# luxometro_16F1709.net
KiCad netlist of a schematic drawn in EAGLE
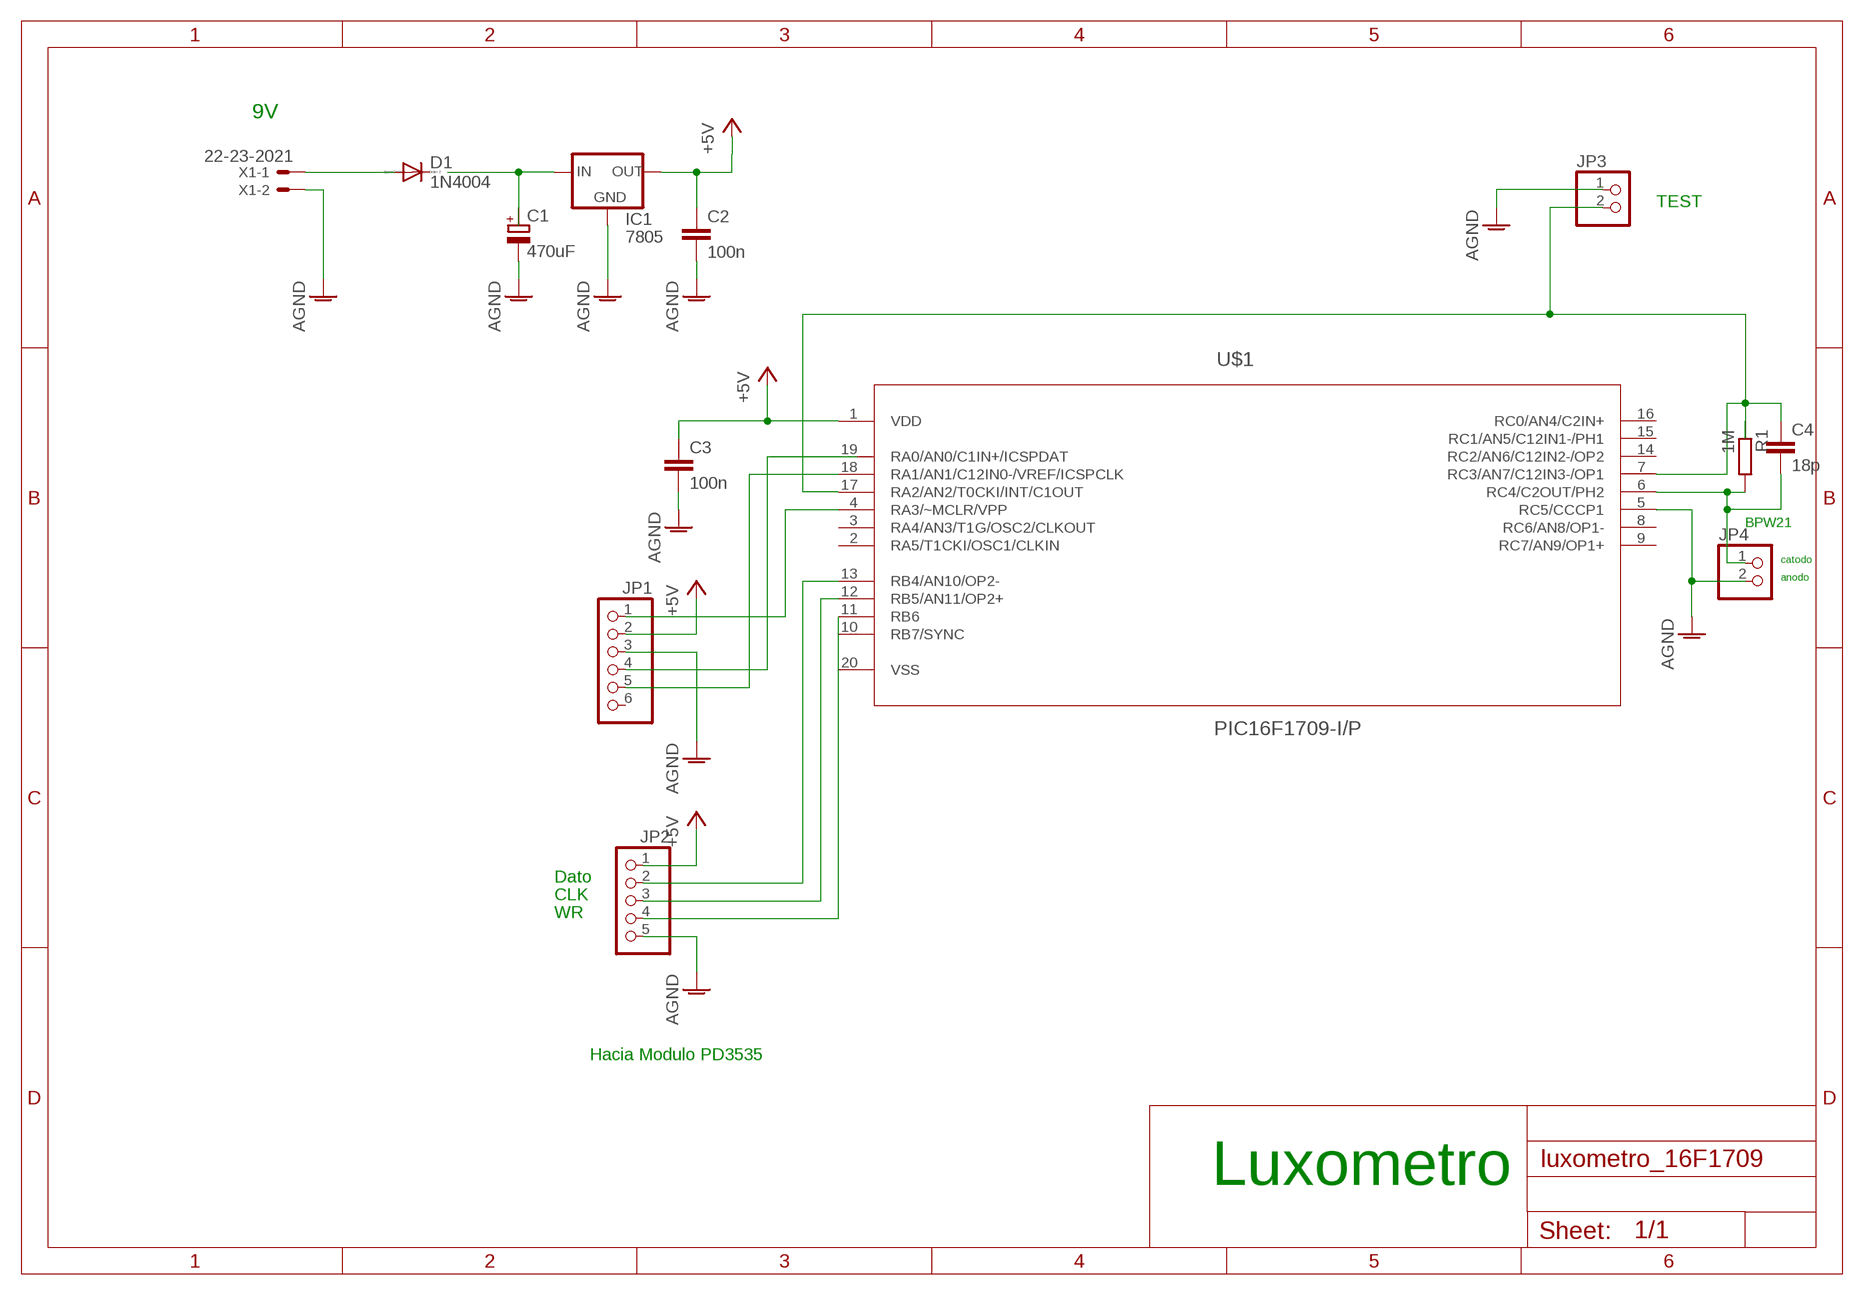
[diagram p0: schematic, sheet 1]

(export (version "E")
  (design (tool "Eeschema 10.0.6"))
  (components
    (comp (ref "C1")
      (value "470uF")
      (footprint "eagle-import:E2,5-6E")
      (libsource (lib "eagle-import") (part "CPOL-EUE2,5-6E"))
    )
    (comp (ref "C2")
      (value "100n")
      (footprint "eagle-import:C050-024X044")
      (libsource (lib "eagle-import") (part "C-EU050-024X044"))
    )
    (comp (ref "C3")
      (value "100n")
      (footprint "eagle-import:C050-024X044")
      (libsource (lib "eagle-import") (part "C-EU050-024X044"))
    )
    (comp (ref "C4")
      (value "18p")
      (footprint "eagle-import:C050-024X044")
      (libsource (lib "eagle-import") (part "C-EU050-024X044"))
    )
    (comp (ref "D1")
      (value "1N4004")
      (footprint "eagle-import:DO41-10")
      (libsource (lib "eagle-import") (part "1N4004"))
    )
    (comp (ref "IC1")
      (value "7805")
      (footprint "eagle-import:78XXL")
      (libsource (lib "eagle-import") (part "78XXL"))
    )
    (comp (ref "JP1")
      (value "PINHD-1X6")
      (footprint "eagle-import:1X06")
      (libsource (lib "eagle-import") (part "PINHD-1X6"))
    )
    (comp (ref "JP2")
      (value "PINHD-1X5")
      (footprint "eagle-import:1X05")
      (libsource (lib "eagle-import") (part "PINHD-1X5"))
    )
    (comp (ref "JP3")
      (value "PINHD-1X2")
      (footprint "eagle-import:1X02")
      (libsource (lib "eagle-import") (part "PINHD-1X2"))
    )
    (comp (ref "JP4")
      (value "PINHD-1X2")
      (footprint "eagle-import:1X02")
      (libsource (lib "eagle-import") (part "PINHD-1X2"))
    )
    (comp (ref "R1")
      (value "1M")
      (footprint "eagle-import:0204_5")
      (libsource (lib "eagle-import") (part "R-EU_0204/5"))
    )
    (comp (ref "U$1")
      (value "PIC16F1709-I/P")
      (footprint "eagle-import:DIP254P762X533-20")
      (fields (field (name "MPN") "PIC16F785-I/P"))
      (libsource (lib "eagle-import") (part "PIC16F785-I/P"))
    )
    (comp (ref "X1")
      (value "22-23-2021")
      (footprint "eagle-import:22-23-2021")
      (fields (field (name "MF") "MOLEX"))
      (libsource (lib "eagle-import") (part "22-23-2021"))
    )
  )
  (nets
    (net (code "1") (name "+5V") (class "Default")
      (node (ref "C2") (pin "1") (pinfunction "1_1") (pintype "passive"))
      (node (ref "C3") (pin "1") (pinfunction "1_1") (pintype "passive"))
      (node (ref "IC1") (pin "OUT") (pinfunction "OUT_OUT") (pintype "passive"))
      (node (ref "JP1") (pin "2") (pinfunction "2_2") (pintype "passive"))
      (node (ref "JP2") (pin "1") (pinfunction "1_1") (pintype "passive"))
      (node (ref "U$1") (pin "1") (pinfunction "VDD_1") (pintype "power_in"))
    )
    (net (code "2") (name "/VSS") (class "Default")
      (node (ref "U$1") (pin "20") (pinfunction "VSS_20") (pintype "power_in"))
    )
    (net (code "3") (name "AGND") (class "Default")
      (node (ref "C1") (pin "-") (pinfunction "-_-") (pintype "passive"))
      (node (ref "C2") (pin "2") (pinfunction "2_2") (pintype "passive"))
      (node (ref "C3") (pin "2") (pinfunction "2_2") (pintype "passive"))
      (node (ref "IC1") (pin "GND") (pinfunction "GND_GND") (pintype "input"))
      (node (ref "JP1") (pin "3") (pinfunction "3_3") (pintype "passive"))
      (node (ref "JP2") (pin "5") (pinfunction "5_5") (pintype "passive"))
      (node (ref "JP3") (pin "1") (pinfunction "1_1") (pintype "passive"))
      (node (ref "JP4") (pin "2") (pinfunction "2_2") (pintype "passive"))
      (node (ref "U$1") (pin "5") (pinfunction "RC5/CCCP1_5") (pintype "bidirectional"))
      (node (ref "X1") (pin "2") (pinfunction "S_2") (pintype "passive"))
    )
    (net (code "4") (name "Net-(C1-Pad+)") (class "Default")
      (node (ref "C1") (pin "+") (pinfunction "+_+") (pintype "passive"))
      (node (ref "IC1") (pin "IN") (pinfunction "IN_IN") (pintype "input"))
    )
    (net (code "5") (name "Net-(U$1-RA1{slash}AN1{slash}C12IN0-{slash}VREF{slash}ICSPCLK)") (class "Default")
      (node (ref "JP1") (pin "5") (pinfunction "5_5") (pintype "passive"))
      (node (ref "U$1") (pin "18") (pinfunction "RA1/AN1/C12IN0-/VREF/ICSPCLK_18") (pintype "bidirectional"))
    )
    (net (code "6") (name "Net-(U$1-RA2{slash}AN2{slash}T0CKI{slash}INT{slash}C1OUT)") (class "Default")
      (node (ref "C4") (pin "1") (pinfunction "1_1") (pintype "passive"))
      (node (ref "JP3") (pin "2") (pinfunction "2_2") (pintype "passive"))
      (node (ref "R1") (pin "1") (pinfunction "1_1") (pintype "passive"))
      (node (ref "U$1") (pin "17") (pinfunction "RA2/AN2/T0CKI/INT/C1OUT_17") (pintype "bidirectional"))
      (node (ref "U$1") (pin "7") (pinfunction "RC3/AN7/C12IN3-/OP1_7") (pintype "bidirectional"))
    )
    (net (code "7") (name "Net-(U$1-RA3{slash}~{MCLR{slash}VPP})") (class "Default")
      (node (ref "JP1") (pin "1") (pinfunction "1_1") (pintype "passive"))
      (node (ref "U$1") (pin "4") (pinfunction "RA3/~{MCLR/VPP}_4") (pintype "bidirectional"))
    )
    (net (code "8") (name "Net-(U$1-RB4{slash}AN10{slash}OP2-)") (class "Default")
      (node (ref "JP2") (pin "2") (pinfunction "2_2") (pintype "passive"))
      (node (ref "U$1") (pin "13") (pinfunction "RB4/AN10/OP2-_13") (pintype "bidirectional"))
    )
    (net (code "9") (name "Net-(U$1-RB5{slash}AN11{slash}OP2+)") (class "Default")
      (node (ref "JP2") (pin "3") (pinfunction "3_3") (pintype "passive"))
      (node (ref "U$1") (pin "12") (pinfunction "RB5/AN11/OP2+_12") (pintype "bidirectional"))
    )
    (net (code "10") (name "Net-(U$1-RB6)") (class "Default")
      (node (ref "JP2") (pin "4") (pinfunction "4_4") (pintype "passive"))
      (node (ref "U$1") (pin "11") (pinfunction "RB6_11") (pintype "bidirectional"))
    )
    (net (code "11") (name "Net-(U$1-RC4{slash}C2OUT{slash}PH2)") (class "Default")
      (node (ref "C4") (pin "2") (pinfunction "2_2") (pintype "passive"))
      (node (ref "JP4") (pin "1") (pinfunction "1_1") (pintype "passive"))
      (node (ref "R1") (pin "2") (pinfunction "2_2") (pintype "passive"))
      (node (ref "U$1") (pin "6") (pinfunction "RC4/C2OUT/PH2_6") (pintype "bidirectional"))
    )
    (net (code "12") (name "Net-(X1A-S)") (class "Default")
      (node (ref "D1") (pin "A") (pinfunction "A_A") (pintype "passive"))
      (node (ref "X1") (pin "1") (pinfunction "S_1") (pintype "passive"))
    )
    (net (code "13") (name "unconnected-(D1-PadC)") (class "Default")
      (node (ref "D1") (pin "C") (pinfunction "C_C") (pintype "passive"))
    )
    (net (code "14") (name "unconnected-(JP1-Pad4)") (class "Default")
      (node (ref "JP1") (pin "4") (pinfunction "4_4") (pintype "passive"))
    )
    (net (code "15") (name "unconnected-(JP1-Pad6)") (class "Default")
      (node (ref "JP1") (pin "6") (pinfunction "6_6") (pintype "passive"))
    )
    (net (code "16") (name "unconnected-(U$1-RA0{slash}AN0{slash}C1IN+{slash}ICSPDAT-Pad19)") (class "Default")
      (node (ref "U$1") (pin "19") (pinfunction "RA0/AN0/C1IN+/ICSPDAT_19") (pintype "bidirectional"))
    )
    (net (code "17") (name "unconnected-(U$1-RA4{slash}AN3{slash}T1G{slash}OSC2{slash}CLKOUT-Pad3)") (class "Default")
      (node (ref "U$1") (pin "3") (pinfunction "RA4/AN3/T1G/OSC2/CLKOUT_3") (pintype "bidirectional"))
    )
    (net (code "18") (name "unconnected-(U$1-RA5{slash}T1CKI{slash}OSC1{slash}CLKIN-Pad2)") (class "Default")
      (node (ref "U$1") (pin "2") (pinfunction "RA5/T1CKI/OSC1/CLKIN_2") (pintype "bidirectional"))
    )
    (net (code "19") (name "unconnected-(U$1-RB7{slash}SYNC-Pad10)") (class "Default")
      (node (ref "U$1") (pin "10") (pinfunction "RB7/SYNC_10") (pintype "bidirectional"))
    )
    (net (code "20") (name "unconnected-(U$1-RC0{slash}AN4{slash}C2IN+-Pad16)") (class "Default")
      (node (ref "U$1") (pin "16") (pinfunction "RC0/AN4/C2IN+_16") (pintype "bidirectional"))
    )
    (net (code "21") (name "unconnected-(U$1-RC1{slash}AN5{slash}C12IN1-{slash}PH1-Pad15)") (class "Default")
      (node (ref "U$1") (pin "15") (pinfunction "RC1/AN5/C12IN1-/PH1_15") (pintype "bidirectional"))
    )
    (net (code "22") (name "unconnected-(U$1-RC2{slash}AN6{slash}C12IN2-{slash}OP2-Pad14)") (class "Default")
      (node (ref "U$1") (pin "14") (pinfunction "RC2/AN6/C12IN2-/OP2_14") (pintype "bidirectional"))
    )
    (net (code "23") (name "unconnected-(U$1-RC6{slash}AN8{slash}OP1--Pad8)") (class "Default")
      (node (ref "U$1") (pin "8") (pinfunction "RC6/AN8/OP1-_8") (pintype "bidirectional"))
    )
    (net (code "24") (name "unconnected-(U$1-RC7{slash}AN9{slash}OP1+-Pad9)") (class "Default")
      (node (ref "U$1") (pin "9") (pinfunction "RC7/AN9/OP1+_9") (pintype "bidirectional"))
    )
  )
)
